# Regulator.net
KiCad netlist of a schematic drawn in EAGLE
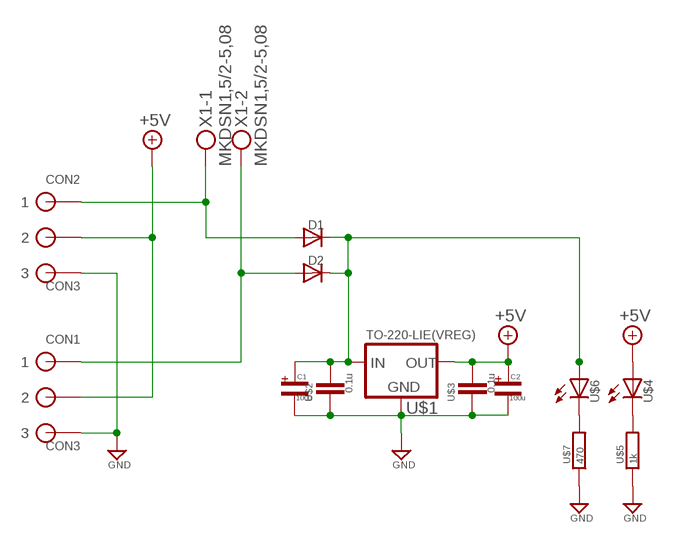
[diagram p0: schematic, sheet 1]

(export (version "E")
  (design (tool "Eeschema 10.0.6"))
  (components
    (comp (ref "C1")
      (value "100u")
      (footprint "eagle-import:D=1,φ=5")
      (libsource (lib "eagle-import") (part "コンデンサ(電解)E2.5-5"))
    )
    (comp (ref "C2")
      (value "100u")
      (footprint "eagle-import:D=1,φ=5")
      (libsource (lib "eagle-import") (part "コンデンサ(電解)E2.5-5"))
    )
    (comp (ref "CON1")
      (value "CON3")
      (footprint "eagle-import:CON3")
      (libsource (lib "eagle-import") (part "CON3"))
    )
    (comp (ref "CON2")
      (value "CON3")
      (footprint "eagle-import:CON3")
      (libsource (lib "eagle-import") (part "CON3"))
    )
    (comp (ref "D1")
      (value "(汎用)D=3")
      (footprint "eagle-import:DO41(D=3)")
      (libsource (lib "eagle-import") (part "(汎用)D=3"))
    )
    (comp (ref "D2")
      (value "(汎用)D=3")
      (footprint "eagle-import:DO41(D=3)")
      (libsource (lib "eagle-import") (part "(汎用)D=3"))
    )
    (comp (ref "U$1")
      (value "TO-220-LIE(VREG)")
      (footprint "eagle-import:TO-220(LIE)")
      (libsource (lib "eagle-import") (part "TO-220-LIE(VREG)"))
    )
    (comp (ref "U$2")
      (value "0.1u")
      (footprint "eagle-import:0805")
      (libsource (lib "eagle-import") (part "コンデンサ0805"))
    )
    (comp (ref "U$3")
      (value "0.1u")
      (footprint "eagle-import:0805")
      (libsource (lib "eagle-import") (part "コンデンサ0805"))
    )
    (comp (ref "U$4")
      (value "LED(砲弾型)3")
      (footprint "eagle-import:LED3MM")
      (libsource (lib "eagle-import") (part "LED(砲弾型)3"))
    )
    (comp (ref "U$5")
      (value "1k")
      (footprint "eagle-import:0805")
      (libsource (lib "eagle-import") (part "抵抗0805"))
    )
    (comp (ref "U$6")
      (value "LED(砲弾型)3")
      (footprint "eagle-import:LED3MM")
      (libsource (lib "eagle-import") (part "LED(砲弾型)3"))
    )
    (comp (ref "U$7")
      (value "470")
      (footprint "eagle-import:0805")
      (libsource (lib "eagle-import") (part "抵抗0805"))
    )
    (comp (ref "X1")
      (value "MKDSN1,5/2-5,08")
      (footprint "eagle-import:MKDSN1,5_2-5,08")
      (libsource (lib "eagle-import") (part "MKDSN1,5/2-5,08"))
    )
  )
  (nets
    (net (code "1") (name "+5V") (class "Default")
      (node (ref "C2") (pin "+") (pinfunction "+_+") (pintype "passive"))
      (node (ref "CON1") (pin "P$2") (pinfunction "2_P$2") (pintype "bidirectional"))
      (node (ref "CON2") (pin "P$2") (pinfunction "2_P$2") (pintype "bidirectional"))
      (node (ref "U$1") (pin "3") (pinfunction "OUT_3") (pintype "passive"))
      (node (ref "U$3") (pin "1") (pinfunction "1_1") (pintype "passive"))
      (node (ref "U$4") (pin "A") (pinfunction "A_A") (pintype "passive"))
    )
    (net (code "2") (name "GND") (class "Default")
      (node (ref "C1") (pin "-") (pinfunction "-_-") (pintype "passive"))
      (node (ref "C2") (pin "-") (pinfunction "-_-") (pintype "passive"))
      (node (ref "CON1") (pin "P$3") (pinfunction "3_P$3") (pintype "bidirectional"))
      (node (ref "CON2") (pin "P$3") (pinfunction "3_P$3") (pintype "bidirectional"))
      (node (ref "U$1") (pin "2") (pinfunction "GND_2") (pintype "input"))
      (node (ref "U$2") (pin "2") (pinfunction "2_2") (pintype "passive"))
      (node (ref "U$3") (pin "2") (pinfunction "2_2") (pintype "passive"))
      (node (ref "U$5") (pin "1") (pinfunction "1_1") (pintype "passive"))
      (node (ref "U$7") (pin "1") (pinfunction "1_1") (pintype "passive"))
    )
    (net (code "3") (name "Net-(CON1-1)") (class "Default")
      (node (ref "CON1") (pin "P$1") (pinfunction "1_P$1") (pintype "bidirectional"))
      (node (ref "D2") (pin "A") (pinfunction "A_A") (pintype "passive"))
      (node (ref "X1") (pin "2") (pinfunction "KL_2") (pintype "passive"))
    )
    (net (code "4") (name "Net-(CON2-1)") (class "Default")
      (node (ref "CON2") (pin "P$1") (pinfunction "1_P$1") (pintype "bidirectional"))
      (node (ref "D1") (pin "A") (pinfunction "A_A") (pintype "passive"))
      (node (ref "X1") (pin "1") (pinfunction "KL_1") (pintype "passive"))
    )
    (net (code "5") (name "Net-(U$1-IN)") (class "Default")
      (node (ref "C1") (pin "+") (pinfunction "+_+") (pintype "passive"))
      (node (ref "D1") (pin "C") (pinfunction "C_C") (pintype "passive"))
      (node (ref "D2") (pin "C") (pinfunction "C_C") (pintype "passive"))
      (node (ref "U$1") (pin "1") (pinfunction "IN_1") (pintype "input"))
      (node (ref "U$2") (pin "1") (pinfunction "1_1") (pintype "passive"))
      (node (ref "U$6") (pin "A") (pinfunction "A_A") (pintype "passive"))
    )
    (net (code "6") (name "Net-(U$4-PadK)") (class "Default")
      (node (ref "U$4") (pin "K") (pinfunction "K_K") (pintype "passive"))
      (node (ref "U$5") (pin "2") (pinfunction "2_2") (pintype "passive"))
    )
    (net (code "7") (name "Net-(U$6-PadK)") (class "Default")
      (node (ref "U$6") (pin "K") (pinfunction "K_K") (pintype "passive"))
      (node (ref "U$7") (pin "2") (pinfunction "2_2") (pintype "passive"))
    )
  )
)
